# power_mux-v7.net
KiCad netlist of a schematic drawn in EAGLE
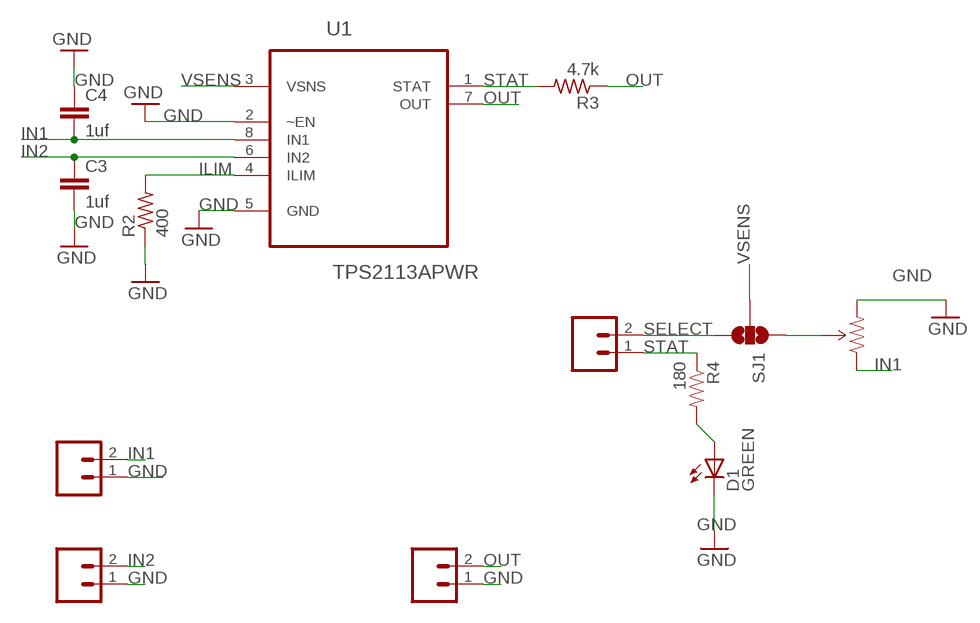
[diagram p0: schematic, sheet 1]

(export (version "E")
  (design (tool "Eeschema 10.0.6"))
  (components
    (comp (ref "C3")
      (value "1uf")
      (footprint "eagle-import:0402-CAP")
      (libsource (lib "eagle-import") (part "CAP0402-CAP"))
    )
    (comp (ref "C4")
      (value "1uf")
      (footprint "eagle-import:0402-CAP")
      (libsource (lib "eagle-import") (part "CAP0402-CAP"))
    )
    (comp (ref "D1")
      (value "GREEN")
      (footprint "eagle-import:LED-0603")
      (libsource (lib "eagle-import") (part "LED-GREEN0603"))
    )
    (comp (ref "JP3")
      (value "M021X02_NO_SILK")
      (footprint "eagle-import:1X02_NO_SILK")
      (libsource (lib "eagle-import") (part "M021X02_NO_SILK"))
    )
    (comp (ref "JP4")
      (value "M021X02_NO_SILK")
      (footprint "eagle-import:1X02_NO_SILK")
      (libsource (lib "eagle-import") (part "M021X02_NO_SILK"))
    )
    (comp (ref "JP5")
      (value "M021X02_NO_SILK")
      (footprint "eagle-import:1X02_NO_SILK")
      (libsource (lib "eagle-import") (part "M021X02_NO_SILK"))
    )
    (comp (ref "JP6")
      (value "M021X02_NO_SILK")
      (footprint "eagle-import:1X02_NO_SILK")
      (libsource (lib "eagle-import") (part "M021X02_NO_SILK"))
    )
    (comp (ref "R1")
      (value "TRIMPOT-PTH-KNOB")
      (footprint "eagle-import:3386U")
      (libsource (lib "eagle-import") (part "TRIMPOT-PTH-KNOB"))
    )
    (comp (ref "R2")
      (value "400")
      (footprint "eagle-import:R0402")
      (libsource (lib "eagle-import") (part "R-US_R0402"))
    )
    (comp (ref "R3")
      (value "4.7k")
      (footprint "eagle-import:R0402")
      (libsource (lib "eagle-import") (part "R-US_R0402"))
    )
    (comp (ref "R4")
      (value "180")
      (footprint "eagle-import:0402-RES")
      (libsource (lib "eagle-import") (part "RESISTOR0402-RES"))
    )
    (comp (ref "SJ1")
      (value "SOLDERJUMPER_2WAYPASTE1&2")
      (footprint "eagle-import:SJ_3_PASTE1&2")
      (libsource (lib "eagle-import") (part "SOLDERJUMPER_2WAYPASTE1&2"))
    )
    (comp (ref "U1")
      (value "TPS2113APWR")
      (footprint "eagle-import:SOP65P640X120-8N")
      (libsource (lib "eagle-import") (part "TPS2113APWR"))
    )
  )
  (nets
    (net (code "1") (name "/ILIM") (class "Default")
      (node (ref "R2") (pin "2") (pinfunction "2_2") (pintype "passive"))
      (node (ref "U1") (pin "4") (pinfunction "ILIM_4") (pintype "input"))
    )
    (net (code "2") (name "/IN1") (class "Default")
      (node (ref "C4") (pin "2") (pinfunction "2_2") (pintype "passive"))
      (node (ref "JP3") (pin "2") (pinfunction "2_2") (pintype "passive"))
      (node (ref "R1") (pin "1") (pinfunction "CCW_1") (pintype "passive"))
      (node (ref "U1") (pin "8") (pinfunction "IN1_8") (pintype "input"))
    )
    (net (code "3") (name "/IN2") (class "Default")
      (node (ref "C3") (pin "1") (pinfunction "1_1") (pintype "passive"))
      (node (ref "JP4") (pin "2") (pinfunction "2_2") (pintype "passive"))
      (node (ref "U1") (pin "6") (pinfunction "IN2_6") (pintype "input"))
    )
    (net (code "4") (name "/OUT") (class "Default")
      (node (ref "JP6") (pin "2") (pinfunction "2_2") (pintype "passive"))
      (node (ref "R3") (pin "1") (pinfunction "1_1") (pintype "passive"))
      (node (ref "U1") (pin "7") (pinfunction "OUT_7") (pintype "output"))
    )
    (net (code "5") (name "/SELECT") (class "Default")
      (node (ref "JP5") (pin "2") (pinfunction "2_2") (pintype "passive"))
      (node (ref "SJ1") (pin "3") (pinfunction "3_3") (pintype "passive"))
    )
    (net (code "6") (name "/STAT") (class "Default")
      (node (ref "JP5") (pin "1") (pinfunction "1_1") (pintype "passive"))
      (node (ref "R3") (pin "2") (pinfunction "2_2") (pintype "passive"))
      (node (ref "R4") (pin "1") (pinfunction "1_1") (pintype "passive"))
      (node (ref "U1") (pin "1") (pinfunction "STAT_1") (pintype "output"))
    )
    (net (code "7") (name "/VSENS") (class "Default")
      (node (ref "SJ1") (pin "2") (pinfunction "2_2") (pintype "passive"))
      (node (ref "U1") (pin "3") (pinfunction "VSNS_3") (pintype "power_in"))
    )
    (net (code "8") (name "GND") (class "Default")
      (node (ref "C3") (pin "2") (pinfunction "2_2") (pintype "passive"))
      (node (ref "C4") (pin "1") (pinfunction "1_1") (pintype "passive"))
      (node (ref "D1") (pin "C") (pinfunction "C_C") (pintype "passive"))
      (node (ref "JP3") (pin "1") (pinfunction "1_1") (pintype "passive"))
      (node (ref "JP4") (pin "1") (pinfunction "1_1") (pintype "passive"))
      (node (ref "JP6") (pin "1") (pinfunction "1_1") (pintype "passive"))
      (node (ref "R1") (pin "3") (pinfunction "CW_3") (pintype "passive"))
      (node (ref "R2") (pin "1") (pinfunction "1_1") (pintype "passive"))
      (node (ref "U1") (pin "2") (pinfunction "~{EN}_2") (pintype "input"))
      (node (ref "U1") (pin "5") (pinfunction "GND_5") (pintype "passive"))
    )
    (net (code "9") (name "Net-(D1-PadA)") (class "Default")
      (node (ref "D1") (pin "A") (pinfunction "A_A") (pintype "passive"))
      (node (ref "R4") (pin "2") (pinfunction "2_2") (pintype "passive"))
    )
    (net (code "10") (name "Net-(R1-WIPER)") (class "Default")
      (node (ref "R1") (pin "2") (pinfunction "WIPER_2") (pintype "passive"))
      (node (ref "SJ1") (pin "1") (pinfunction "1_1") (pintype "passive"))
    )
  )
)
